# 1_POWER.net
KiCad netlist of a schematic drawn in Altium Designer
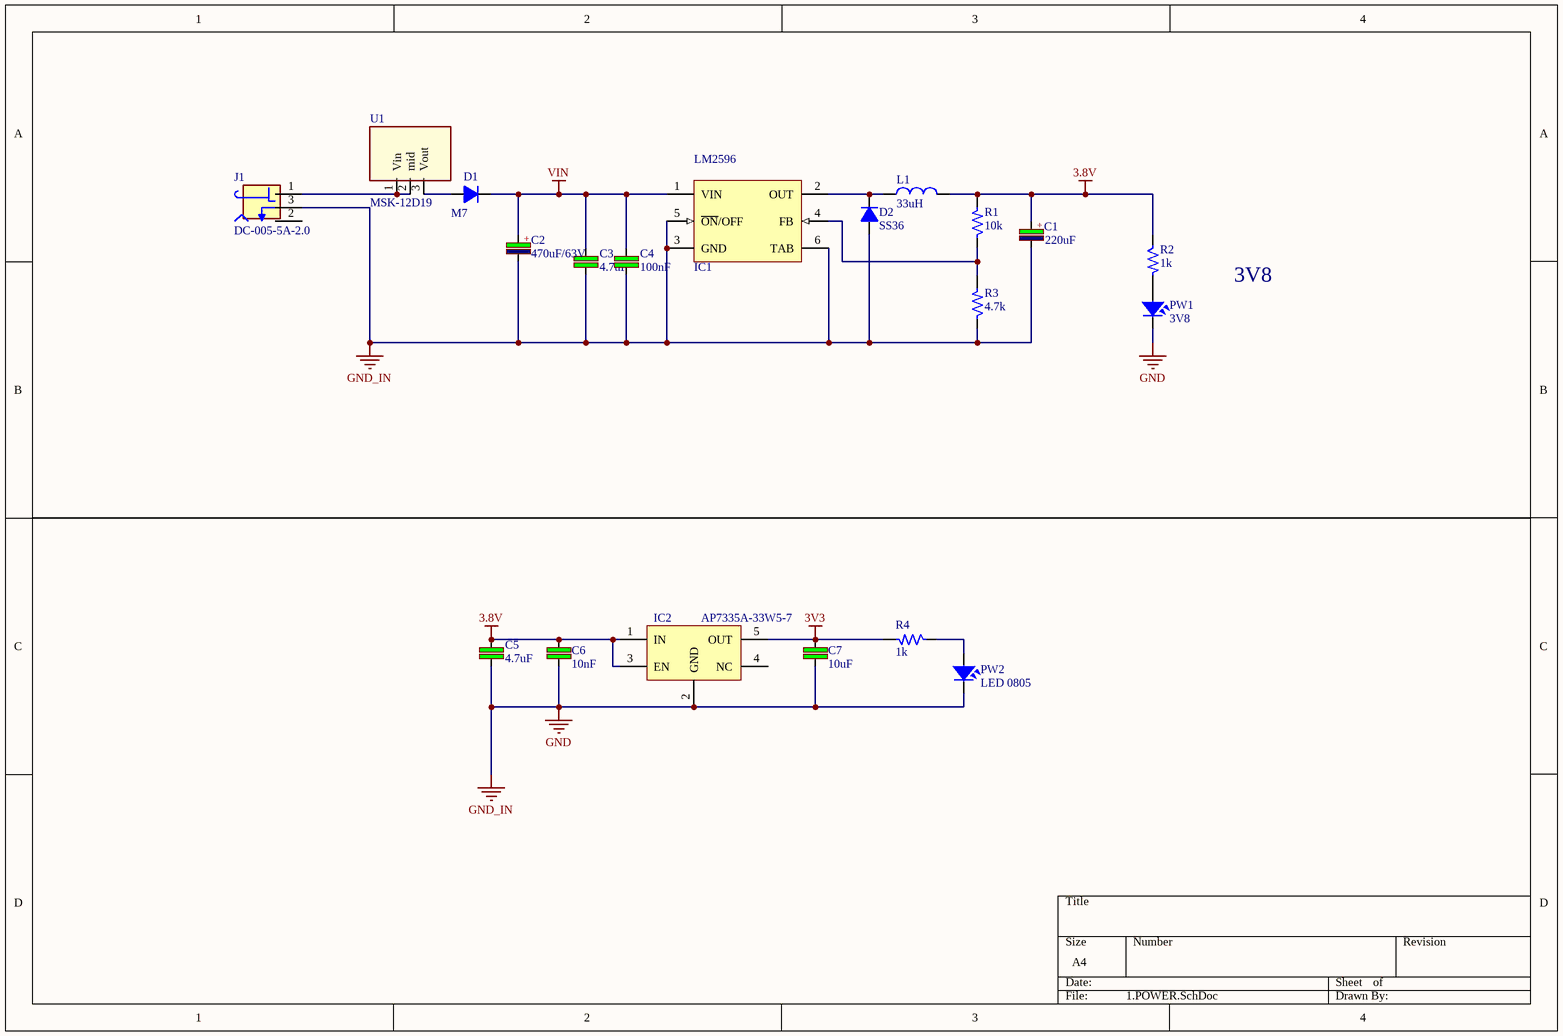
[diagram p0: 1.POWER.SchDoc]

(export (version "E")
  (design (tool "Eeschema 10.0.6"))
  (components
    (comp (ref "C1")
      (value "220uF")
      (footprint "EEFSDE")
      (description "220µF Molded Tantalum Polymer Capacitor 16V 2917 (7343 Metric) 40mOhm @ 100kHz")
      (fields
        (field (name "MANUFACTURER") "AVX Corporation")
        (field (name "PART NUMBER") "TCME227M016R0040E")
      )
      (libsource (lib "Anh_Trung") (part "CP5"))
    )
    (comp (ref "C2")
      (value "470uF/63V")
      (footprint "CAP-ALU-SMD-C")
      (description "Cap 470uF/63V")
      (libsource (lib "Main") (part "CP3"))
    )
    (comp (ref "C3")
      (value "4.7uF")
      (footprint "C-0805")
      (description "4.7µF ±10% 35V Ceramic Capacitor X5R 0805 (2012 Metric)")
      (fields
        (field (name "MANUFACTURER") "Samsung Electro-Mechanics")
        (field (name "PART NUMBER") "CL21A475KLCLQNC")
      )
      (libsource (lib "") (part "C_1"))
    )
    (comp (ref "C4")
      (value "100nF")
      (footprint "C-0805")
      (description "4.7µF ±10% 35V Ceramic Capacitor X5R 0805 (2012 Metric)")
      (fields
        (field (name "MANUFACTURER") "Samsung Electro-Mechanics")
        (field (name "PART NUMBER") "CL21A475KLCLQNC")
      )
      (libsource (lib "") (part "C_1"))
    )
    (comp (ref "C5")
      (value "4.7uF")
      (footprint "C-0805")
      (description "4.7µF ±10% 35V Ceramic Capacitor X5R 0805 (2012 Metric)")
      (fields
        (field (name "MANUFACTURER") "Samsung Electro-Mechanics")
        (field (name "PART NUMBER") "CL21A475KLCLQNC")
      )
      (libsource (lib "") (part "C_1"))
    )
    (comp (ref "C6")
      (value "10nF")
      (footprint "C-0805")
      (description "Cap SMD")
      (fields
        (field (name "MANUFACTURER") "Samsung Electro-Mechanics")
        (field (name "PART NUMBER") "CL21A106KPFNNNG")
      )
      (libsource (lib "Anh_Trung") (part "C"))
    )
    (comp (ref "C7")
      (value "10uF")
      (footprint "C-0805")
      (description "Cap SMD")
      (fields
        (field (name "MANUFACTURER") "Samsung Electro-Mechanics")
        (field (name "PART NUMBER") "CL21A106KPFNNNG")
      )
      (libsource (lib "Anh_Trung") (part "C"))
    )
    (comp (ref "D1")
      (value "M7")
      (footprint "LED-0805-Blue")
      (description "Diode 1A")
      (libsource (lib "Main") (part "D1A"))
    )
    (comp (ref "D2")
      (value "SS36")
      (footprint "LED-0805-Blue")
      (description "Diode Schottky 40V 3A Surface Mount DO-214AC (SMA)")
      (fields
        (field (name "MANUFACTURER") "Vishay General Semiconductor - Diodes Division")
        (field (name "PART NUMBER") "B340A-M3/61T")
      )
      (libsource (lib "Main") (part "B340A"))
    )
    (comp (ref "IC1")
      (value "LM2596")
      (footprint "TO-263")
      (description "LM2576")
      (libsource (lib "Main") (part "LM2576"))
    )
    (comp (ref "IC2")
      (value "AP7335A-33W5-7")
      (footprint "SOT23-5")
      (libsource (lib "Anh_Trung") (part "AP7335A-33W5-7"))
    )
    (comp (ref "J1")
      (value "DC-005-5A-2.0")
      (footprint "XKB_DC-005-5A-2.0")
      (description "DC Power Receptacle Jack, Through Holeï¼ŒRight Angle")
      (fields (field (name "MF") "XKB Industrial Precision"))
      (libsource (lib "DC-005-5A-2.0") (part "DC-005-5A-2.0"))
    )
    (comp (ref "L1")
      (value "33uH")
      (footprint "Inductor_SMD")
      (description "22µH Shielded Inductor 1.65A 96mOhm Max Nonstandard")
      (fields (field (name "MANUFACTURER") "Bourns Inc.") (field (name "PART NUMBER") "SRR0745A-220M"))
      (libsource (lib "Main") (part "L1"))
    )
    (comp (ref "PW1")
      (value "3V8")
      (footprint "LED-0805-Blue")
      (description "LED RED DIFFUSED 0805 SMD")
      (fields
        (field (name "MANUFACTURER") "OSRAM Opto Semiconductors Inc.")
        (field (name "PART NUMBER") "LS R976-NR-1")
      )
      (libsource (lib "Anh_Trung") (part "LED"))
    )
    (comp (ref "PW2")
      (value "LED 0805")
      (footprint "LED-0805-Blue")
      (description "LED RED DIFFUSED 0805 SMD")
      (fields
        (field (name "MANUFACTURER") "OSRAM Opto Semiconductors Inc.")
        (field (name "PART NUMBER") "LS R976-NR-1")
      )
      (libsource (lib "Main") (part "LED"))
    )
    (comp (ref "R1")
      (value "10k")
      (footprint "R-0805")
      (description "RES SMD 10K OHM 1% 1/8W 0805")
      (fields (field (name "MANUFACTURER") "Yageo") (field (name "PART NUMBER") "RC0805FR-0710KL"))
      (libsource (lib "Anh_Trung") (part "R"))
    )
    (comp (ref "R2")
      (value "1k")
      (footprint "R-0805")
      (description "Resistor 1/4W")
      (fields (field (name "MANUFACTURER") "Yageo") (field (name "PART NUMBER") "RC0805FR-071KL"))
      (libsource (lib "Anh_Trung") (part "R"))
    )
    (comp (ref "R3")
      (value "4.7k")
      (footprint "R-0805")
      (description "RES SMD 3.3K OHM 1% 1/8W 0805")
      (fields (field (name "MANUFACTURER") "Yageo") (field (name "PART NUMBER") "RC0805FR-073K3L"))
      (libsource (lib "Anh_Trung") (part "R"))
    )
    (comp (ref "R4")
      (value "1k")
      (footprint "R-0805")
      (description "Resistor 1/4W")
      (fields (field (name "MANUFACTURER") "Yageo") (field (name "PART NUMBER") "RC0805FR-071KL"))
      (libsource (lib "Anh_Trung") (part "R"))
    )
    (comp (ref "U1") (value "MSK-12D19") (footprint "Switch") (libsource (lib "SIM_devkit") (part "switch")))
  )
  (nets
    (net (code "1") (name "3.8V") (class "Default")
      (node (ref "C1") (pin "1") (pinfunction "1_1") (pintype "passive"))
      (node (ref "C5") (pin "2") (pinfunction "2_2") (pintype "passive"))
      (node (ref "C6") (pin "1") (pinfunction "1_1") (pintype "passive"))
      (node (ref "IC2") (pin "1") (pinfunction "IN_1") (pintype "passive"))
      (node (ref "IC2") (pin "3") (pinfunction "EN_3") (pintype "passive"))
      (node (ref "L1") (pin "2") (pinfunction "2_2") (pintype "passive"))
      (node (ref "R1") (pin "2") (pinfunction "2_2") (pintype "passive"))
      (node (ref "R2") (pin "1") (pinfunction "1_1") (pintype "passive"))
    )
    (net (code "2") (name "3V3") (class "Default")
      (node (ref "C7") (pin "1") (pinfunction "1_1") (pintype "passive"))
      (node (ref "IC2") (pin "5") (pinfunction "OUT_5") (pintype "passive"))
      (node (ref "R4") (pin "2") (pinfunction "2_2") (pintype "passive"))
    )
    (net (code "3") (name "GND") (class "Default")
      (node (ref "C1") (pin "2") (pinfunction "2_2") (pintype "passive"))
      (node (ref "C2") (pin "2") (pinfunction "2_2") (pintype "passive"))
      (node (ref "C3") (pin "1") (pinfunction "1_1") (pintype "passive"))
      (node (ref "C4") (pin "1") (pinfunction "1_1") (pintype "passive"))
      (node (ref "C5") (pin "1") (pinfunction "1_1") (pintype "passive"))
      (node (ref "C6") (pin "2") (pinfunction "2_2") (pintype "passive"))
      (node (ref "C7") (pin "2") (pinfunction "2_2") (pintype "passive"))
      (node (ref "D2") (pin "1") (pinfunction "A_1") (pintype "passive"))
      (node (ref "IC1") (pin "3") (pinfunction "GND_3") (pintype "power_in"))
      (node (ref "IC1") (pin "5") (pinfunction "~{ON}/OFF_5") (pintype "input"))
      (node (ref "IC1") (pin "6") (pinfunction "TAB_6") (pintype "power_in"))
      (node (ref "IC2") (pin "2") (pinfunction "GND_2") (pintype "passive"))
      (node (ref "J1") (pin "3") (pinfunction "3_3") (pintype "passive"))
      (node (ref "PW1") (pin "2") (pinfunction "2_2") (pintype "passive"))
      (node (ref "PW2") (pin "2") (pinfunction "2_2") (pintype "passive"))
      (node (ref "R3") (pin "1") (pinfunction "1_1") (pintype "passive"))
    )
    (net (code "4") (name "Net-(D1-A)") (class "Default")
      (node (ref "D1") (pin "1") (pinfunction "A_1") (pintype "passive"))
      (node (ref "U1") (pin "3") (pinfunction "Vout_3") (pintype "passive"))
    )
    (net (code "5") (name "Net-(D2-K)") (class "Default")
      (node (ref "D2") (pin "2") (pinfunction "K_2") (pintype "passive"))
      (node (ref "IC1") (pin "2") (pinfunction "OUT_2") (pintype "power_in"))
      (node (ref "L1") (pin "1") (pinfunction "1_1") (pintype "passive"))
    )
    (net (code "6") (name "Net-(IC1-FB)") (class "Default")
      (node (ref "IC1") (pin "4") (pinfunction "FB_4") (pintype "input"))
      (node (ref "R1") (pin "1") (pinfunction "1_1") (pintype "passive"))
      (node (ref "R3") (pin "2") (pinfunction "2_2") (pintype "passive"))
    )
    (net (code "7") (name "Net-(PW1-Pad1)") (class "Default")
      (node (ref "PW1") (pin "1") (pinfunction "1_1") (pintype "passive"))
      (node (ref "R2") (pin "2") (pinfunction "2_2") (pintype "passive"))
    )
    (net (code "8") (name "Net-(PW2-Pad1)") (class "Default")
      (node (ref "PW2") (pin "1") (pinfunction "1_1") (pintype "passive"))
      (node (ref "R4") (pin "1") (pinfunction "1_1") (pintype "passive"))
    )
    (net (code "9") (name "Net-(U1-Vin)") (class "Default")
      (node (ref "J1") (pin "1") (pinfunction "1_1") (pintype "passive"))
      (node (ref "U1") (pin "1") (pinfunction "Vin_1") (pintype "passive"))
      (node (ref "U1") (pin "2") (pinfunction "mid_2") (pintype "passive"))
    )
    (net (code "10") (name "VIN") (class "Default")
      (node (ref "C2") (pin "1") (pinfunction "1_1") (pintype "passive"))
      (node (ref "C3") (pin "2") (pinfunction "2_2") (pintype "passive"))
      (node (ref "C4") (pin "2") (pinfunction "2_2") (pintype "passive"))
      (node (ref "D1") (pin "2") (pinfunction "K_2") (pintype "passive"))
      (node (ref "IC1") (pin "1") (pinfunction "VIN_1") (pintype "power_in"))
    )
    (net (code "11") (name "unconnected-(IC2-NC-Pad4)") (class "Default")
      (node (ref "IC2") (pin "4") (pinfunction "NC_4") (pintype "passive"))
    )
    (net (code "12") (name "unconnected-(J1-Pad2)") (class "Default")
      (node (ref "J1") (pin "2") (pinfunction "2_2") (pintype "passive"))
    )
  )
)
